# Power12V.net
KiCad netlist of a schematic drawn in Altium Designer
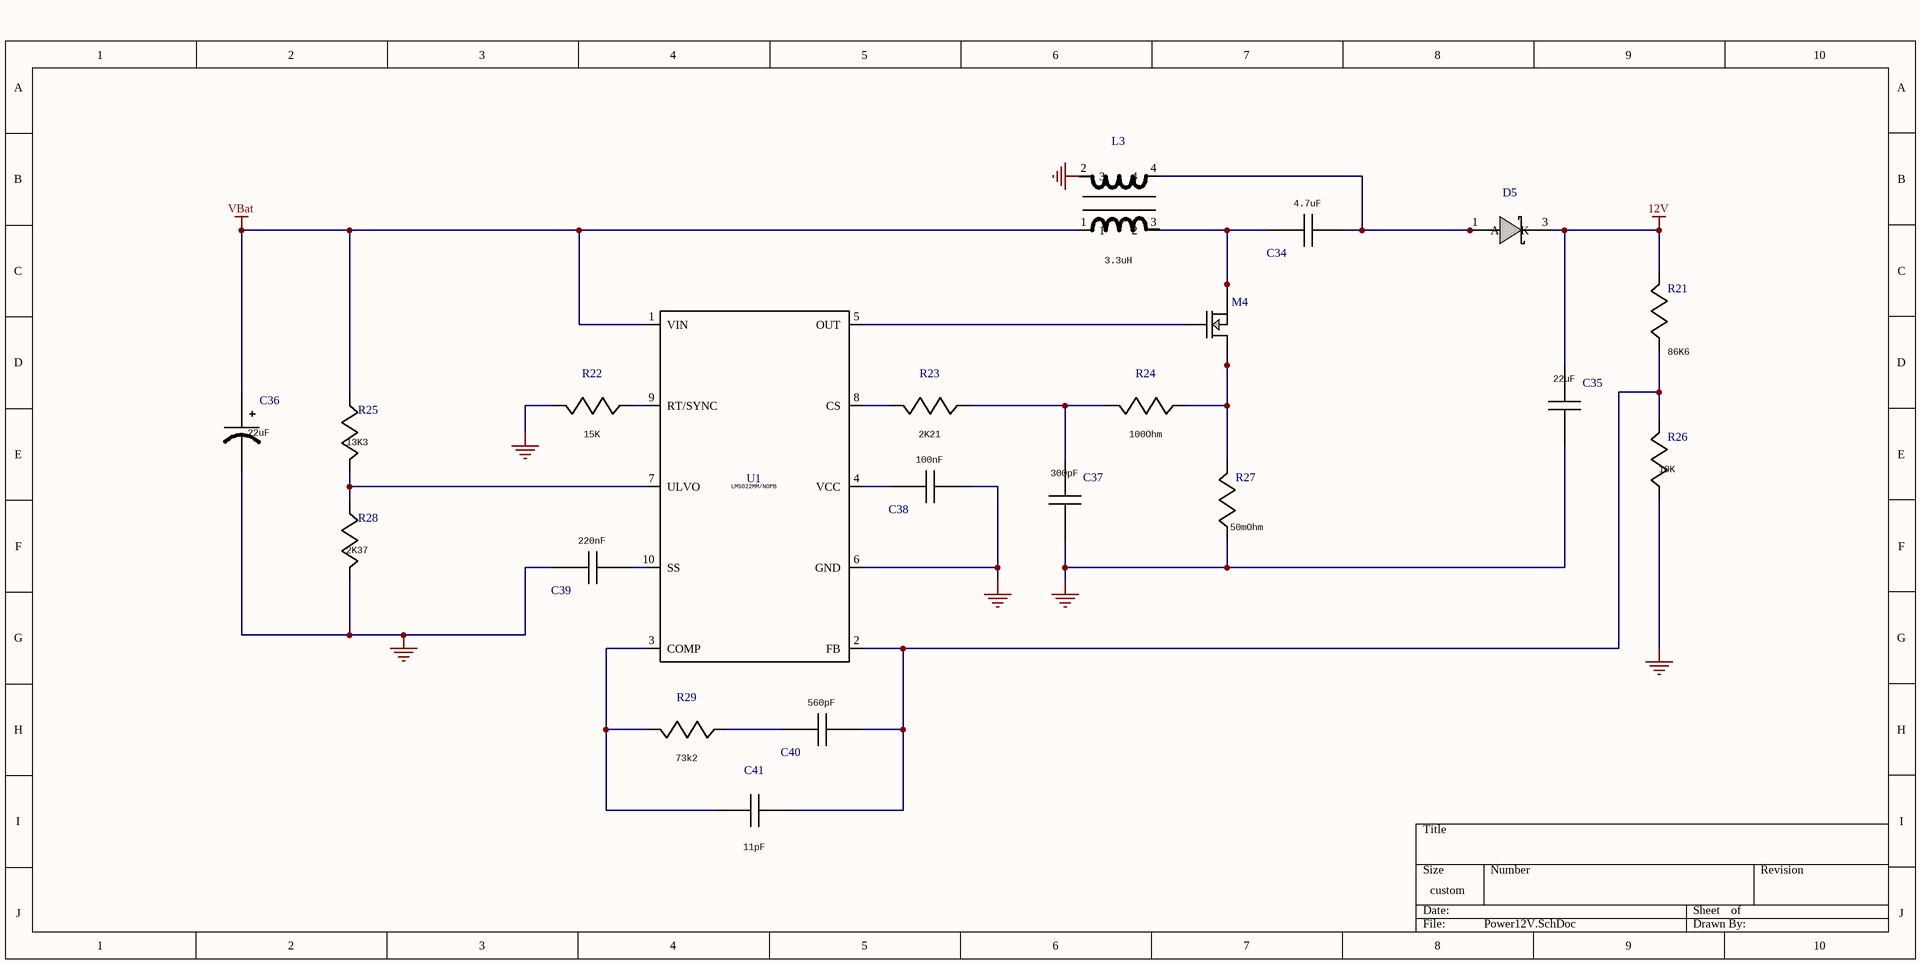
[diagram p0: Power12V.SchDoc]

(export (version "E")
  (design (tool "Eeschema 10.0.6"))
  (components
    (comp (ref "C34")
      (value "4.7uF")
      (footprint "0805")
      (description "Imported")
      (fields
        (field (name "MANUFACTURER_PART_NUMBER") "GRM21BR61E475MA12L")
        (field (name "Comment") "GRM21BR61E475MA1")
      )
      (libsource (lib "TI WEBENCH") (part "GRM21BR61E475MA1"))
    )
    (comp (ref "C35")
      (value "22uF")
      (footprint "1210")
      (description "Imported")
      (fields
        (field (name "MANUFACTURER_PART_NUMBER") "GRM32ER61C226KE20L")
        (field (name "Comment") "GRM32ER61C226KE2")
      )
      (libsource (lib "TI WEBENCH") (part "GRM32ER61C226KE2"))
    )
    (comp (ref "C36")
      (value "22uF")
      (footprint "3528-21")
      (description "Imported")
      (fields (field (name "MANUFACTURER_PART_NUMBER") "TPSB226K020R0400"))
      (libsource (lib "TI WEBENCH") (part "TPSB226K020R0400"))
    )
    (comp (ref "C37")
      (value "300pF")
      (footprint "1608")
      (description "Imported")
      (fields
        (field (name "MANUFACTURER_PART_NUMBER") "GRM1555C1E301JA01D")
        (field (name "Comment") "GRM1555C1E301JA0")
      )
      (libsource (lib "TI WEBENCH") (part "GRM1555C1E301JA0"))
    )
    (comp (ref "C38")
      (value "100nF")
      (footprint "1608")
      (description "Imported")
      (fields
        (field (name "MANUFACTURER_PART_NUMBER") "GRM155R61C104KA88D")
        (field (name "Comment") "GRM155R61C104KA8")
      )
      (libsource (lib "TI WEBENCH") (part "GRM155R61C104KA8"))
    )
    (comp (ref "C39")
      (value "220nF")
      (footprint "1608")
      (description "Imported")
      (fields
        (field (name "MANUFACTURER_PART_NUMBER") "GRM155R71C224KA12D")
        (field (name "Comment") "GRM155R71C224KA1")
      )
      (libsource (lib "TI WEBENCH") (part "GRM155R71C224KA1"))
    )
    (comp (ref "C40")
      (value "560pF")
      (footprint "1608")
      (description "Imported")
      (fields
        (field (name "MANUFACTURER_PART_NUMBER") "CC0805KRX7R9BB561")
        (field (name "Comment") "CC0805KRX7R9BB56")
      )
      (libsource (lib "TI WEBENCH") (part "CC0805KRX7R9BB56"))
    )
    (comp (ref "C41")
      (value "11pF")
      (footprint "1608")
      (description "Imported")
      (fields (field (name "MANUFACTURER_PART_NUMBER") "C0603C0G1E110G"))
      (libsource (lib "TI WEBENCH") (part "C0603C0G1E110G"))
    )
    (comp (ref "D5")
      (value "PDS760-13")
      (footprint "PowerDI5")
      (description "Imported")
      (libsource (lib "TI WEBENCH") (part "PDS760-13"))
    )
    (comp (ref "L3")
      (value "3.3uH")
      (footprint "DRQ127")
      (description "Imported")
      (fields (field (name "MANUFACTURER_PART_NUMBER") "DRQ127-3R3-R"))
      (libsource (lib "TI WEBENCH") (part "DRQ127-3R3-R"))
    )
    (comp (ref "M4")
      (value "CSD16340Q3")
      (footprint "TRANS_NexFET_Q3")
      (description "Imported")
      (libsource (lib "TI WEBENCH") (part "CSD16340Q3"))
    )
    (comp (ref "R21")
      (value "86K6")
      (footprint "1608")
      (description "Imported")
      (fields (field (name "MANUFACTURER_PART_NUMBER") "CRCW040286K6FKED"))
      (libsource (lib "TI WEBENCH") (part "CRCW040286K6FKED"))
    )
    (comp (ref "R22")
      (value "15K")
      (footprint "1608")
      (description "Imported")
      (fields (field (name "MANUFACTURER_PART_NUMBER") "CRCW040215K0FKED"))
      (libsource (lib "TI WEBENCH") (part "CRCW040215K0FKED"))
    )
    (comp (ref "R23")
      (value "2K21")
      (footprint "1608")
      (description "Imported")
      (fields (field (name "MANUFACTURER_PART_NUMBER") "CRCW04022K21FKED"))
      (libsource (lib "TI WEBENCH") (part "CRCW04022K21FKED"))
    )
    (comp (ref "R24")
      (value "100Ohm")
      (footprint "1608")
      (description "Imported")
      (fields (field (name "MANUFACTURER_PART_NUMBER") "CRCW0402100RFKED"))
      (libsource (lib "TI WEBENCH") (part "CRCW0402100RFKED"))
    )
    (comp (ref "R25")
      (value "13K3")
      (footprint "1608")
      (description "Imported")
      (fields (field (name "MANUFACTURER_PART_NUMBER") "CRCW040213K3FKED"))
      (libsource (lib "TI WEBENCH") (part "CRCW040213K3FKED"))
    )
    (comp (ref "R26")
      (value "10K")
      (footprint "1608")
      (description "Imported")
      (fields (field (name "MANUFACTURER_PART_NUMBER") "CRCW040210K0FKED"))
      (libsource (lib "TI WEBENCH") (part "CRCW040210K0FKED"))
    )
    (comp (ref "R27")
      (value "50mOhm")
      (footprint "2010")
      (description "Imported")
      (fields (field (name "MANUFACTURER_PART_NUMBER") "CSRN2010FK50L0"))
      (libsource (lib "TI WEBENCH") (part "CSRN2010FK50L0"))
    )
    (comp (ref "R28")
      (value "2K37")
      (footprint "1608")
      (description "Imported")
      (fields (field (name "MANUFACTURER_PART_NUMBER") "CRCW04022K37FKED"))
      (libsource (lib "TI WEBENCH") (part "CRCW04022K37FKED"))
    )
    (comp (ref "R29")
      (value "73k2")
      (footprint "1608")
      (description "Imported")
      (fields (field (name "MANUFACTURER_PART_NUMBER") "CRCW040273K2FKED"))
      (libsource (lib "TI WEBENCH") (part "CRCW040273K2FKED"))
    )
    (comp (ref "U1")
      (value "LM5022MM/NOPB")
      (footprint "MUB10A")
      (description "Imported")
      (fields (field (name "MANUFACTURER_PART_NUMBER") "LM5022MM/NOPB"))
      (libsource (lib "TI WEBENCH") (part "LM5022MM/NOPB"))
    )
  )
  (nets
    (net (code "1") (name "12V") (class "Default")
      (node (ref "C35") (pin "1") (pinfunction "1_1") (pintype "passive"))
      (node (ref "D5") (pin "3") (pinfunction "K_3") (pintype "passive"))
      (node (ref "R21") (pin "1") (pinfunction "1_1") (pintype "passive"))
    )
    (net (code "2") (name "GND") (class "Default")
      (node (ref "C35") (pin "2") (pinfunction "2_2") (pintype "passive"))
      (node (ref "C36") (pin "2") (pinfunction "-_2") (pintype "passive"))
      (node (ref "C37") (pin "2") (pinfunction "2_2") (pintype "passive"))
      (node (ref "C38") (pin "2") (pinfunction "2_2") (pintype "passive"))
      (node (ref "C39") (pin "2") (pinfunction "2_2") (pintype "passive"))
      (node (ref "L3") (pin "2") (pinfunction "3_2") (pintype "passive"))
      (node (ref "R22") (pin "1") (pinfunction "1_1") (pintype "passive"))
      (node (ref "R26") (pin "2") (pinfunction "2_2") (pintype "passive"))
      (node (ref "R27") (pin "2") (pinfunction "2_2") (pintype "passive"))
      (node (ref "R28") (pin "1") (pinfunction "1_1") (pintype "passive"))
      (node (ref "U1") (pin "6") (pinfunction "GND_6") (pintype "passive"))
    )
    (net (code "3") (name "Net-(C34-Pad1)") (class "Default")
      (node (ref "C34") (pin "1") (pinfunction "1_1") (pintype "passive"))
      (node (ref "D5") (pin "1") (pinfunction "A_1") (pintype "passive"))
      (node (ref "D5") (pin "2") (pinfunction "A_2") (pintype "passive"))
      (node (ref "L3") (pin "4") (pinfunction "4_4") (pintype "passive"))
    )
    (net (code "4") (name "Net-(C37-Pad1)") (class "Default")
      (node (ref "C37") (pin "1") (pinfunction "1_1") (pintype "passive"))
      (node (ref "R23") (pin "2") (pinfunction "2_2") (pintype "passive"))
      (node (ref "R24") (pin "1") (pinfunction "1_1") (pintype "passive"))
    )
    (net (code "5") (name "Net-(C40-Pad2)") (class "Default")
      (node (ref "C40") (pin "2") (pinfunction "2_2") (pintype "passive"))
      (node (ref "R29") (pin "2") (pinfunction "2_2") (pintype "passive"))
    )
    (net (code "6") (name "Net-(L3-2)") (class "Default")
      (node (ref "C34") (pin "2") (pinfunction "2_2") (pintype "passive"))
      (node (ref "L3") (pin "3") (pinfunction "2_3") (pintype "passive"))
      (node (ref "M4") (pin "1") (pinfunction "Source_1") (pintype "passive"))
      (node (ref "M4") (pin "2") (pinfunction "Source_2") (pintype "passive"))
      (node (ref "M4") (pin "3") (pinfunction "Source_3") (pintype "passive"))
    )
    (net (code "7") (name "Net-(M4-Drain-Pad5)") (class "Default")
      (node (ref "M4") (pin "5") (pinfunction "Drain_5") (pintype "passive"))
      (node (ref "M4") (pin "6") (pinfunction "Drain_6") (pintype "passive"))
      (node (ref "M4") (pin "7") (pinfunction "Drain_7") (pintype "passive"))
      (node (ref "M4") (pin "8") (pinfunction "Drain_8") (pintype "passive"))
      (node (ref "M4") (pin "9") (pinfunction "Drain_9") (pintype "passive"))
      (node (ref "R24") (pin "2") (pinfunction "2_2") (pintype "passive"))
      (node (ref "R27") (pin "1") (pinfunction "1_1") (pintype "passive"))
    )
    (net (code "8") (name "Net-(M4-Gate)") (class "Default")
      (node (ref "M4") (pin "4") (pinfunction "Gate_4") (pintype "passive"))
      (node (ref "U1") (pin "5") (pinfunction "OUT_5") (pintype "passive"))
    )
    (net (code "9") (name "Net-(U1-COMP)") (class "Default")
      (node (ref "C41") (pin "2") (pinfunction "2_2") (pintype "passive"))
      (node (ref "R29") (pin "1") (pinfunction "1_1") (pintype "passive"))
      (node (ref "U1") (pin "3") (pinfunction "COMP_3") (pintype "passive"))
    )
    (net (code "10") (name "Net-(U1-CS)") (class "Default")
      (node (ref "R23") (pin "1") (pinfunction "1_1") (pintype "passive"))
      (node (ref "U1") (pin "8") (pinfunction "CS_8") (pintype "passive"))
    )
    (net (code "11") (name "Net-(U1-FB)") (class "Default")
      (node (ref "C40") (pin "1") (pinfunction "1_1") (pintype "passive"))
      (node (ref "C41") (pin "1") (pinfunction "1_1") (pintype "passive"))
      (node (ref "R21") (pin "2") (pinfunction "2_2") (pintype "passive"))
      (node (ref "R26") (pin "1") (pinfunction "1_1") (pintype "passive"))
      (node (ref "U1") (pin "2") (pinfunction "FB_2") (pintype "passive"))
    )
    (net (code "12") (name "Net-(U1-RT{slash}SYNC)") (class "Default")
      (node (ref "R22") (pin "2") (pinfunction "2_2") (pintype "passive"))
      (node (ref "U1") (pin "9") (pinfunction "RT/SYNC_9") (pintype "passive"))
    )
    (net (code "13") (name "Net-(U1-SS)") (class "Default")
      (node (ref "C39") (pin "1") (pinfunction "1_1") (pintype "passive"))
      (node (ref "U1") (pin "10") (pinfunction "SS_10") (pintype "passive"))
    )
    (net (code "14") (name "Net-(U1-ULVO)") (class "Default")
      (node (ref "R25") (pin "1") (pinfunction "1_1") (pintype "passive"))
      (node (ref "R28") (pin "2") (pinfunction "2_2") (pintype "passive"))
      (node (ref "U1") (pin "7") (pinfunction "ULVO_7") (pintype "passive"))
    )
    (net (code "15") (name "Net-(U1-VCC)") (class "Default")
      (node (ref "C38") (pin "1") (pinfunction "1_1") (pintype "passive"))
      (node (ref "U1") (pin "4") (pinfunction "VCC_4") (pintype "passive"))
    )
    (net (code "16") (name "VBat") (class "Default")
      (node (ref "C36") (pin "1") (pinfunction "+_1") (pintype "passive"))
      (node (ref "L3") (pin "1") (pinfunction "1_1") (pintype "passive"))
      (node (ref "R25") (pin "2") (pinfunction "2_2") (pintype "passive"))
      (node (ref "U1") (pin "1") (pinfunction "VIN_1") (pintype "passive"))
    )
  )
)
